# LEDs.net
KiCad netlist of a schematic drawn in EAGLE
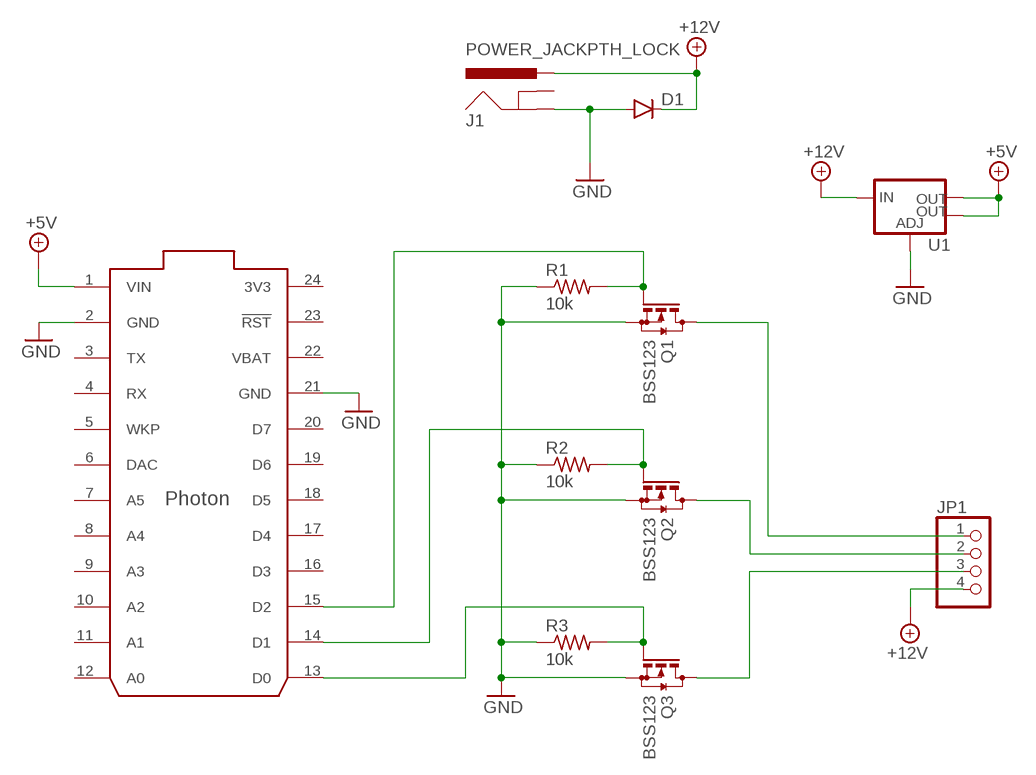
[diagram p0: schematic, sheet 1]

(export (version "E")
  (design (tool "Eeschema 10.0.6"))
  (components
    (comp (ref "D1")
      (value "DIODESMA")
      (footprint "eagle-import:SMA-DIODE")
      (libsource (lib "eagle-import") (part "DIODESMA"))
    )
    (comp (ref "J1")
      (value "POWER_JACKPTH_LOCK")
      (footprint "eagle-import:POWER_JACK_PTH_LOCK")
      (libsource (lib "eagle-import") (part "POWER_JACKPTH_LOCK"))
    )
    (comp (ref "JP1")
      (value "PINHD-1X4/90")
      (footprint "eagle-import:1X04_90")
      (libsource (lib "eagle-import") (part "PINHD-1X4/90"))
    )
    (comp (ref "Q1")
      (value "BSS123")
      (footprint "eagle-import:SOT23")
      (libsource (lib "eagle-import") (part "BSS123"))
    )
    (comp (ref "Q2")
      (value "BSS123")
      (footprint "eagle-import:SOT23")
      (libsource (lib "eagle-import") (part "BSS123"))
    )
    (comp (ref "Q3")
      (value "BSS123")
      (footprint "eagle-import:SOT23")
      (libsource (lib "eagle-import") (part "BSS123"))
    )
    (comp (ref "R1")
      (value "10k")
      (footprint "eagle-import:M0805")
      (libsource (lib "eagle-import") (part "R-US_M0805"))
    )
    (comp (ref "R2")
      (value "10k")
      (footprint "eagle-import:M0805")
      (libsource (lib "eagle-import") (part "R-US_M0805"))
    )
    (comp (ref "R3")
      (value "10k")
      (footprint "eagle-import:M0805")
      (libsource (lib "eagle-import") (part "R-US_M0805"))
    )
    (comp (ref "U$1")
      (value "PHOTON_WITH_HEADERS")
      (footprint "eagle-import:PHOTON")
      (libsource (lib "eagle-import") (part "PHOTON_WITH_HEADERS"))
    )
    (comp (ref "U1")
      (value "V_REG_LM1117SOT223")
      (footprint "eagle-import:SOT223")
      (libsource (lib "eagle-import") (part "V_REG_LM1117SOT223"))
    )
  )
  (nets
    (net (code "1") (name "+5V") (class "Default")
      (node (ref "U$1") (pin "1") (pinfunction "VIN_1") (pintype "power_in"))
      (node (ref "U1") (pin "2") (pinfunction "OUT_2") (pintype "output"))
      (node (ref "U1") (pin "4") (pinfunction "OUT_4") (pintype "output"))
    )
    (net (code "2") (name "+12V") (class "Default")
      (node (ref "D1") (pin "C") (pinfunction "C_C") (pintype "passive"))
      (node (ref "J1") (pin "PWR") (pinfunction "PWR_PWR") (pintype "bidirectional"))
      (node (ref "JP1") (pin "4") (pinfunction "4_4") (pintype "passive"))
      (node (ref "U1") (pin "3") (pinfunction "IN_3") (pintype "input"))
    )
    (net (code "3") (name "/3V3") (class "Default")
      (node (ref "U$1") (pin "24") (pinfunction "3V3_24") (pintype "power_in"))
    )
    (net (code "4") (name "/VBAT") (class "Default")
      (node (ref "U$1") (pin "22") (pinfunction "VBAT_22") (pintype "power_in"))
    )
    (net (code "5") (name "GND") (class "Default")
      (node (ref "D1") (pin "A") (pinfunction "A_A") (pintype "passive"))
      (node (ref "J1") (pin "GND") (pinfunction "GND_GND") (pintype "bidirectional"))
      (node (ref "Q1") (pin "2") (pinfunction "S_2") (pintype "passive"))
      (node (ref "Q2") (pin "2") (pinfunction "S_2") (pintype "passive"))
      (node (ref "Q3") (pin "2") (pinfunction "S_2") (pintype "passive"))
      (node (ref "R1") (pin "1") (pinfunction "1_1") (pintype "passive"))
      (node (ref "R2") (pin "1") (pinfunction "1_1") (pintype "passive"))
      (node (ref "R3") (pin "1") (pinfunction "1_1") (pintype "passive"))
      (node (ref "U$1") (pin "2") (pinfunction "GND_2") (pintype "power_in"))
      (node (ref "U$1") (pin "21") (pinfunction "GND_21") (pintype "power_in"))
      (node (ref "U1") (pin "1") (pinfunction "ADJ_1") (pintype "input"))
    )
    (net (code "6") (name "Net-(Q1-D)") (class "Default")
      (node (ref "JP1") (pin "1") (pinfunction "1_1") (pintype "passive"))
      (node (ref "Q1") (pin "3") (pinfunction "D_3") (pintype "passive"))
    )
    (net (code "7") (name "Net-(Q1-G)") (class "Default")
      (node (ref "Q1") (pin "1") (pinfunction "G_1") (pintype "passive"))
      (node (ref "R1") (pin "2") (pinfunction "2_2") (pintype "passive"))
      (node (ref "U$1") (pin "15") (pinfunction "D2_15") (pintype "bidirectional"))
    )
    (net (code "8") (name "Net-(Q2-D)") (class "Default")
      (node (ref "JP1") (pin "2") (pinfunction "2_2") (pintype "passive"))
      (node (ref "Q2") (pin "3") (pinfunction "D_3") (pintype "passive"))
    )
    (net (code "9") (name "Net-(Q2-G)") (class "Default")
      (node (ref "Q2") (pin "1") (pinfunction "G_1") (pintype "passive"))
      (node (ref "R2") (pin "2") (pinfunction "2_2") (pintype "passive"))
      (node (ref "U$1") (pin "14") (pinfunction "D1_14") (pintype "bidirectional"))
    )
    (net (code "10") (name "Net-(Q3-D)") (class "Default")
      (node (ref "JP1") (pin "3") (pinfunction "3_3") (pintype "passive"))
      (node (ref "Q3") (pin "3") (pinfunction "D_3") (pintype "passive"))
    )
    (net (code "11") (name "Net-(Q3-G)") (class "Default")
      (node (ref "Q3") (pin "1") (pinfunction "G_1") (pintype "passive"))
      (node (ref "R3") (pin "2") (pinfunction "2_2") (pintype "passive"))
      (node (ref "U$1") (pin "13") (pinfunction "D0_13") (pintype "bidirectional"))
    )
    (net (code "12") (name "unconnected-(J1-PadGNDBREAK)") (class "Default")
      (node (ref "J1") (pin "GNDBREAK") (pinfunction "GNDBREAK_GNDBREAK") (pintype "bidirectional"))
    )
    (net (code "13") (name "unconnected-(U$1-A0-Pad12)") (class "Default")
      (node (ref "U$1") (pin "12") (pinfunction "A0_12") (pintype "bidirectional"))
    )
    (net (code "14") (name "unconnected-(U$1-A1-Pad11)") (class "Default")
      (node (ref "U$1") (pin "11") (pinfunction "A1_11") (pintype "bidirectional"))
    )
    (net (code "15") (name "unconnected-(U$1-A2-Pad10)") (class "Default")
      (node (ref "U$1") (pin "10") (pinfunction "A2_10") (pintype "bidirectional"))
    )
    (net (code "16") (name "unconnected-(U$1-A3-Pad9)") (class "Default")
      (node (ref "U$1") (pin "9") (pinfunction "A3_9") (pintype "bidirectional"))
    )
    (net (code "17") (name "unconnected-(U$1-A4-Pad8)") (class "Default")
      (node (ref "U$1") (pin "8") (pinfunction "A4_8") (pintype "bidirectional"))
    )
    (net (code "18") (name "unconnected-(U$1-A5-Pad7)") (class "Default")
      (node (ref "U$1") (pin "7") (pinfunction "A5_7") (pintype "bidirectional"))
    )
    (net (code "19") (name "unconnected-(U$1-D3-Pad16)") (class "Default")
      (node (ref "U$1") (pin "16") (pinfunction "D3_16") (pintype "bidirectional"))
    )
    (net (code "20") (name "unconnected-(U$1-D4-Pad17)") (class "Default")
      (node (ref "U$1") (pin "17") (pinfunction "D4_17") (pintype "bidirectional"))
    )
    (net (code "21") (name "unconnected-(U$1-D5-Pad18)") (class "Default")
      (node (ref "U$1") (pin "18") (pinfunction "D5_18") (pintype "bidirectional"))
    )
    (net (code "22") (name "unconnected-(U$1-D6-Pad19)") (class "Default")
      (node (ref "U$1") (pin "19") (pinfunction "D6_19") (pintype "bidirectional"))
    )
    (net (code "23") (name "unconnected-(U$1-D7-Pad20)") (class "Default")
      (node (ref "U$1") (pin "20") (pinfunction "D7_20") (pintype "bidirectional"))
    )
    (net (code "24") (name "unconnected-(U$1-DAC-Pad6)") (class "Default")
      (node (ref "U$1") (pin "6") (pinfunction "DAC_6") (pintype "bidirectional"))
    )
    (net (code "25") (name "unconnected-(U$1-RX-Pad4)") (class "Default")
      (node (ref "U$1") (pin "4") (pinfunction "RX_4") (pintype "bidirectional"))
    )
    (net (code "26") (name "unconnected-(U$1-TX-Pad3)") (class "Default")
      (node (ref "U$1") (pin "3") (pinfunction "TX_3") (pintype "bidirectional"))
    )
    (net (code "27") (name "unconnected-(U$1-WKP-Pad5)") (class "Default")
      (node (ref "U$1") (pin "5") (pinfunction "WKP_5") (pintype "bidirectional"))
    )
    (net (code "28") (name "unconnected-(U$1-~{RST}-Pad23)") (class "Default")
      (node (ref "U$1") (pin "23") (pinfunction "~{RST}_23") (pintype "bidirectional"))
    )
  )
)
